# BPR-301_Circuit.net
KiCad netlist of a schematic drawn in EAGLE
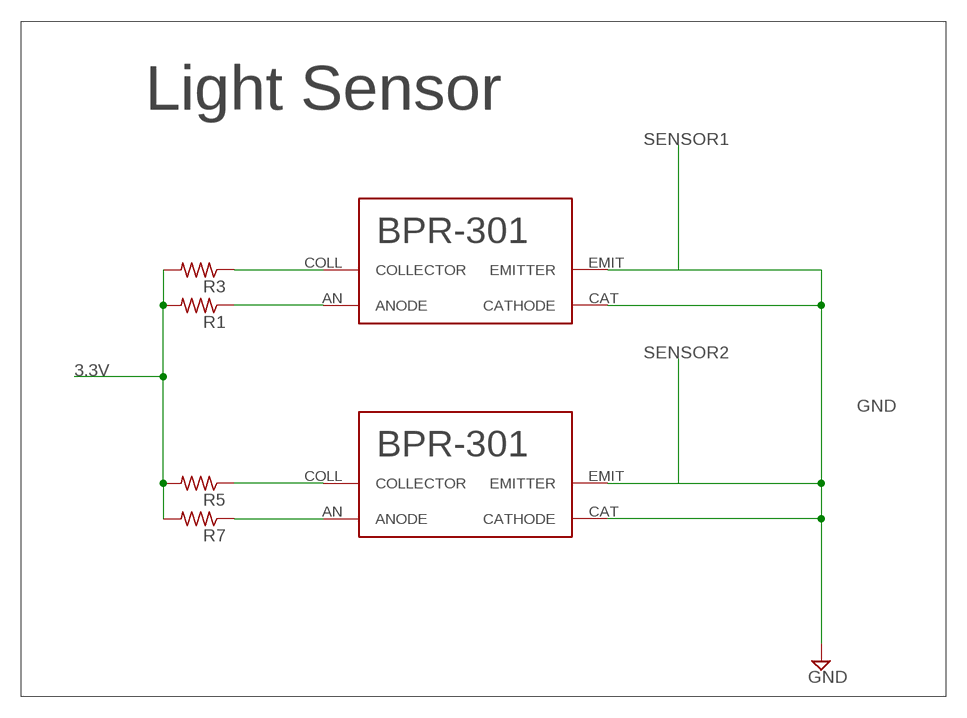
[diagram p0: schematic, sheet 1]

(export (version "E")
  (design (tool "Eeschema 10.0.6"))
  (components
    (comp (ref "R1")
      (value "R-US_R0402")
      (footprint "eagle-import:R0402")
      (libsource (lib "eagle-import") (part "R-US_R0402"))
    )
    (comp (ref "R3")
      (value "R-US_R0402")
      (footprint "eagle-import:R0402")
      (libsource (lib "eagle-import") (part "R-US_R0402"))
    )
    (comp (ref "R5")
      (value "R-US_R0402")
      (footprint "eagle-import:R0402")
      (libsource (lib "eagle-import") (part "R-US_R0402"))
    )
    (comp (ref "R7")
      (value "R-US_R0402")
      (footprint "eagle-import:R0402")
      (libsource (lib "eagle-import") (part "R-US_R0402"))
    )
    (comp (ref "U$1")
      (value "BPR-301")
      (footprint "eagle-import:BPR-301")
      (libsource (lib "eagle-import") (part "BPR-301"))
    )
    (comp (ref "U$2")
      (value "BPR-301")
      (footprint "eagle-import:BPR-301")
      (libsource (lib "eagle-import") (part "BPR-301"))
    )
  )
  (nets
    (net (code "1") (name "/3.3V") (class "Default")
      (node (ref "R1") (pin "2") (pinfunction "2_2") (pintype "passive"))
      (node (ref "R3") (pin "2") (pinfunction "2_2") (pintype "passive"))
      (node (ref "R5") (pin "2") (pinfunction "2_2") (pintype "passive"))
      (node (ref "R7") (pin "2") (pinfunction "2_2") (pintype "passive"))
    )
    (net (code "4") (name "GND") (class "Default")
      (node (ref "U$1") (pin "CAT") (pinfunction "CATHODE_CAT") (pintype "bidirectional"))
      (node (ref "U$1") (pin "EMIT") (pinfunction "EMITTER_EMIT") (pintype "bidirectional"))
      (node (ref "U$2") (pin "CAT") (pinfunction "CATHODE_CAT") (pintype "bidirectional"))
      (node (ref "U$2") (pin "EMIT") (pinfunction "EMITTER_EMIT") (pintype "bidirectional"))
    )
    (net (code "5") (name "Net-(U$1-ANODE)") (class "Default")
      (node (ref "R7") (pin "1") (pinfunction "1_1") (pintype "passive"))
      (node (ref "U$1") (pin "AN") (pinfunction "ANODE_AN") (pintype "bidirectional"))
    )
    (net (code "6") (name "Net-(U$1-COLLECTOR)") (class "Default")
      (node (ref "R5") (pin "1") (pinfunction "1_1") (pintype "passive"))
      (node (ref "U$1") (pin "COLL") (pinfunction "COLLECTOR_COLL") (pintype "bidirectional"))
    )
    (net (code "7") (name "Net-(U$2-ANODE)") (class "Default")
      (node (ref "R1") (pin "1") (pinfunction "1_1") (pintype "passive"))
      (node (ref "U$2") (pin "AN") (pinfunction "ANODE_AN") (pintype "bidirectional"))
    )
    (net (code "8") (name "Net-(U$2-COLLECTOR)") (class "Default")
      (node (ref "R3") (pin "1") (pinfunction "1_1") (pintype "passive"))
      (node (ref "U$2") (pin "COLL") (pinfunction "COLLECTOR_COLL") (pintype "bidirectional"))
    )
  )
)
